# controls.net
KiCad netlist of a schematic drawn in EAGLE
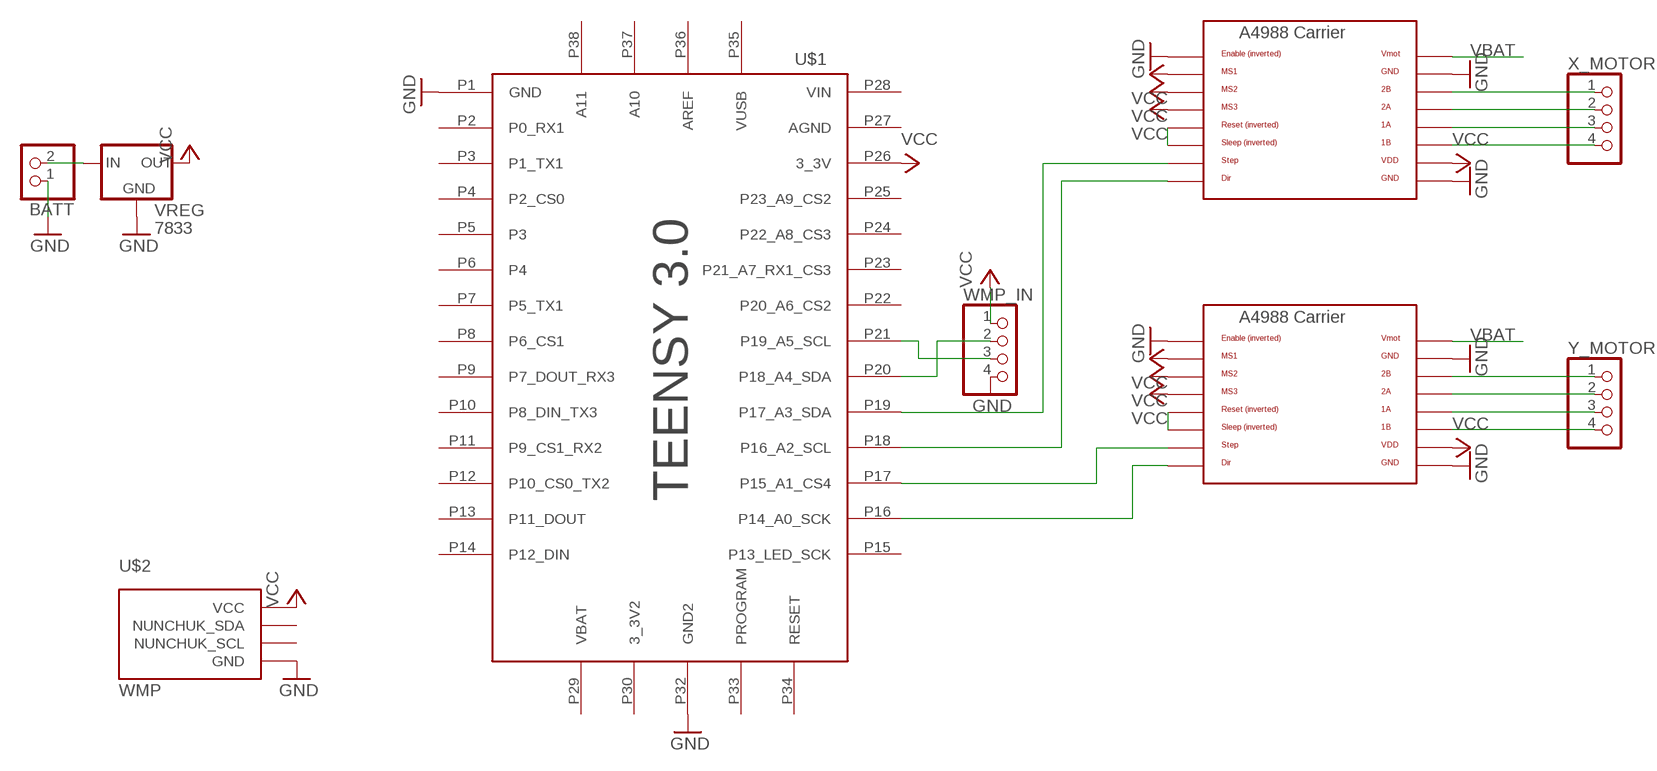
[diagram p0: schematic, sheet 1]

(export (version "E")
  (design (tool "Eeschema 10.0.6"))
  (components
    (comp (ref "BATT")
      (value "PINHD-1X2")
      (footprint "eagle-import:1X02")
      (libsource (lib "eagle-import") (part "PINHD-1X2"))
    )
    (comp (ref "U$1")
      (value "TEENSY3")
      (footprint "eagle-import:TEENSY3_BRD")
      (libsource (lib "eagle-import") (part "TEENSY3"))
    )
    (comp (ref "U$2")
      (value "WMP")
      (footprint "eagle-import:WMP")
      (libsource (lib "eagle-import") (part "WMP"))
    )
    (comp (ref "VREG")
      (value "7833")
      (footprint "eagle-import:78LXX")
      (libsource (lib "eagle-import") (part "78LXX"))
    )
    (comp (ref "WMP_IN")
      (value "PINHD-1X4/90")
      (footprint "eagle-import:1X04_90")
      (libsource (lib "eagle-import") (part "PINHD-1X4/90"))
    )
    (comp (ref "X_DRIVE")
      (value "POLOLU_A4983CARRIER")
      (footprint "eagle-import:A4988BREAKOUT")
      (libsource (lib "eagle-import") (part "POLOLU_A4983CARRIER"))
    )
    (comp (ref "X_MOTOR")
      (value "PINHD-1X4/90")
      (footprint "eagle-import:1X04_90")
      (libsource (lib "eagle-import") (part "PINHD-1X4/90"))
    )
    (comp (ref "Y_DRIVE")
      (value "POLOLU_A4983CARRIER")
      (footprint "eagle-import:A4988BREAKOUT")
      (libsource (lib "eagle-import") (part "POLOLU_A4983CARRIER"))
    )
    (comp (ref "Y_MOTOR")
      (value "PINHD-1X4/90")
      (footprint "eagle-import:1X04_90")
      (libsource (lib "eagle-import") (part "PINHD-1X4/90"))
    )
  )
  (nets
    (net (code "1") (name "/VBAT") (class "Default")
      (node (ref "BATT") (pin "2") (pinfunction "2_2") (pintype "passive"))
      (node (ref "VREG") (pin "IN") (pinfunction "IN_IN") (pintype "input"))
      (node (ref "X_DRIVE") (pin "VMOT") (pinfunction "VMOT_VMOT") (pintype "power_in"))
      (node (ref "Y_DRIVE") (pin "VMOT") (pinfunction "VMOT_VMOT") (pintype "power_in"))
    )
    (net (code "2") (name "GND") (class "Default")
      (node (ref "BATT") (pin "1") (pinfunction "1_1") (pintype "passive"))
      (node (ref "U$1") (pin "P1") (pinfunction "GND_P1") (pintype "bidirectional"))
      (node (ref "U$1") (pin "P32") (pinfunction "GND2_P32") (pintype "bidirectional"))
      (node (ref "U$2") (pin "GND") (pinfunction "GND_GND") (pintype "power_in"))
      (node (ref "VREG") (pin "GND") (pinfunction "GND_GND") (pintype "input"))
      (node (ref "WMP_IN") (pin "4") (pinfunction "4_4") (pintype "passive"))
      (node (ref "X_DRIVE") (pin "EN") (pinfunction "EN_EN") (pintype "input"))
      (node (ref "X_DRIVE") (pin "GND") (pinfunction "GND_GND") (pintype "power_in"))
      (node (ref "X_DRIVE") (pin "GND@0") (pinfunction "GND_GND@0") (pintype "power_in"))
      (node (ref "Y_DRIVE") (pin "EN") (pinfunction "EN_EN") (pintype "input"))
      (node (ref "Y_DRIVE") (pin "GND") (pinfunction "GND_GND") (pintype "power_in"))
      (node (ref "Y_DRIVE") (pin "GND@0") (pinfunction "GND_GND@0") (pintype "power_in"))
    )
    (net (code "3") (name "Net-(U$1-P14_A0_SCK)") (class "Default")
      (node (ref "U$1") (pin "P16") (pinfunction "P14_A0_SCK_P16") (pintype "bidirectional"))
      (node (ref "Y_DRIVE") (pin "DIR") (pinfunction "DIR_DIR") (pintype "input"))
    )
    (net (code "4") (name "Net-(U$1-P15_A1_CS4)") (class "Default")
      (node (ref "U$1") (pin "P17") (pinfunction "P15_A1_CS4_P17") (pintype "bidirectional"))
      (node (ref "Y_DRIVE") (pin "STEP") (pinfunction "STEP_STEP") (pintype "input"))
    )
    (net (code "5") (name "Net-(U$1-P16_A2_SCL)") (class "Default")
      (node (ref "U$1") (pin "P18") (pinfunction "P16_A2_SCL_P18") (pintype "bidirectional"))
      (node (ref "X_DRIVE") (pin "DIR") (pinfunction "DIR_DIR") (pintype "input"))
    )
    (net (code "6") (name "Net-(U$1-P17_A3_SDA)") (class "Default")
      (node (ref "U$1") (pin "P19") (pinfunction "P17_A3_SDA_P19") (pintype "bidirectional"))
      (node (ref "X_DRIVE") (pin "STEP") (pinfunction "STEP_STEP") (pintype "input"))
    )
    (net (code "7") (name "Net-(U$1-P18_A4_SDA)") (class "Default")
      (node (ref "U$1") (pin "P20") (pinfunction "P18_A4_SDA_P20") (pintype "bidirectional"))
      (node (ref "WMP_IN") (pin "2") (pinfunction "2_2") (pintype "passive"))
    )
    (net (code "8") (name "Net-(U$1-P19_A5_SCL)") (class "Default")
      (node (ref "U$1") (pin "P21") (pinfunction "P19_A5_SCL_P21") (pintype "bidirectional"))
      (node (ref "WMP_IN") (pin "3") (pinfunction "3_3") (pintype "passive"))
    )
    (net (code "9") (name "Net-(X_DRIVE-Pad1A)") (class "Default")
      (node (ref "X_DRIVE") (pin "1A") (pinfunction "1A_1A") (pintype "output"))
      (node (ref "X_MOTOR") (pin "3") (pinfunction "3_3") (pintype "passive"))
    )
    (net (code "10") (name "Net-(X_DRIVE-Pad1B)") (class "Default")
      (node (ref "X_DRIVE") (pin "1B") (pinfunction "1B_1B") (pintype "output"))
      (node (ref "X_MOTOR") (pin "4") (pinfunction "4_4") (pintype "passive"))
    )
    (net (code "11") (name "Net-(X_DRIVE-Pad2A)") (class "Default")
      (node (ref "X_DRIVE") (pin "2A") (pinfunction "2A_2A") (pintype "output"))
      (node (ref "X_MOTOR") (pin "2") (pinfunction "2_2") (pintype "passive"))
    )
    (net (code "12") (name "Net-(X_DRIVE-Pad2B)") (class "Default")
      (node (ref "X_DRIVE") (pin "2B") (pinfunction "2B_2B") (pintype "output"))
      (node (ref "X_MOTOR") (pin "1") (pinfunction "1_1") (pintype "passive"))
    )
    (net (code "13") (name "Net-(X_DRIVE-SLEEP)") (class "Default")
      (node (ref "X_DRIVE") (pin "RST") (pinfunction "RST_RST") (pintype "input"))
      (node (ref "X_DRIVE") (pin "SLP") (pinfunction "SLEEP_SLP") (pintype "input"))
    )
    (net (code "14") (name "Net-(Y_DRIVE-Pad1A)") (class "Default")
      (node (ref "Y_DRIVE") (pin "1A") (pinfunction "1A_1A") (pintype "output"))
      (node (ref "Y_MOTOR") (pin "3") (pinfunction "3_3") (pintype "passive"))
    )
    (net (code "15") (name "Net-(Y_DRIVE-Pad1B)") (class "Default")
      (node (ref "Y_DRIVE") (pin "1B") (pinfunction "1B_1B") (pintype "output"))
      (node (ref "Y_MOTOR") (pin "4") (pinfunction "4_4") (pintype "passive"))
    )
    (net (code "16") (name "Net-(Y_DRIVE-Pad2A)") (class "Default")
      (node (ref "Y_DRIVE") (pin "2A") (pinfunction "2A_2A") (pintype "output"))
      (node (ref "Y_MOTOR") (pin "2") (pinfunction "2_2") (pintype "passive"))
    )
    (net (code "17") (name "Net-(Y_DRIVE-Pad2B)") (class "Default")
      (node (ref "Y_DRIVE") (pin "2B") (pinfunction "2B_2B") (pintype "output"))
      (node (ref "Y_MOTOR") (pin "1") (pinfunction "1_1") (pintype "passive"))
    )
    (net (code "18") (name "Net-(Y_DRIVE-SLEEP)") (class "Default")
      (node (ref "Y_DRIVE") (pin "RST") (pinfunction "RST_RST") (pintype "input"))
      (node (ref "Y_DRIVE") (pin "SLP") (pinfunction "SLEEP_SLP") (pintype "input"))
    )
    (net (code "19") (name "VCC") (class "Default")
      (node (ref "U$1") (pin "P26") (pinfunction "3_3V_P26") (pintype "bidirectional"))
      (node (ref "U$2") (pin "VCC") (pinfunction "VCC_VCC") (pintype "power_in"))
      (node (ref "VREG") (pin "OUT") (pinfunction "OUT_OUT") (pintype "passive"))
      (node (ref "WMP_IN") (pin "1") (pinfunction "1_1") (pintype "passive"))
      (node (ref "X_DRIVE") (pin "MS1") (pinfunction "MS1_MS1") (pintype "input"))
      (node (ref "X_DRIVE") (pin "MS2") (pinfunction "MS2_MS2") (pintype "input"))
      (node (ref "X_DRIVE") (pin "MS3") (pinfunction "MS3_MS3") (pintype "input"))
      (node (ref "X_DRIVE") (pin "VDD") (pinfunction "VDD_VDD") (pintype "power_in"))
      (node (ref "Y_DRIVE") (pin "MS1") (pinfunction "MS1_MS1") (pintype "input"))
      (node (ref "Y_DRIVE") (pin "MS2") (pinfunction "MS2_MS2") (pintype "input"))
      (node (ref "Y_DRIVE") (pin "MS3") (pinfunction "MS3_MS3") (pintype "input"))
      (node (ref "Y_DRIVE") (pin "VDD") (pinfunction "VDD_VDD") (pintype "power_in"))
    )
    (net (code "20") (name "unconnected-(U$1-3_3V2-PadP30)") (class "Default")
      (node (ref "U$1") (pin "P30") (pinfunction "3_3V2_P30") (pintype "bidirectional"))
    )
    (net (code "21") (name "unconnected-(U$1-A10-PadP37)") (class "Default")
      (node (ref "U$1") (pin "P37") (pinfunction "A10_P37") (pintype "bidirectional"))
    )
    (net (code "22") (name "unconnected-(U$1-A11-PadP38)") (class "Default")
      (node (ref "U$1") (pin "P38") (pinfunction "A11_P38") (pintype "bidirectional"))
    )
    (net (code "23") (name "unconnected-(U$1-AGND-PadP27)") (class "Default")
      (node (ref "U$1") (pin "P27") (pinfunction "AGND_P27") (pintype "bidirectional"))
    )
    (net (code "24") (name "unconnected-(U$1-AREF-PadP36)") (class "Default")
      (node (ref "U$1") (pin "P36") (pinfunction "AREF_P36") (pintype "bidirectional"))
    )
    (net (code "25") (name "unconnected-(U$1-P0_RX1-PadP2)") (class "Default")
      (node (ref "U$1") (pin "P2") (pinfunction "P0_RX1_P2") (pintype "bidirectional"))
    )
    (net (code "26") (name "unconnected-(U$1-P1_TX1-PadP3)") (class "Default")
      (node (ref "U$1") (pin "P3") (pinfunction "P1_TX1_P3") (pintype "bidirectional"))
    )
    (net (code "27") (name "unconnected-(U$1-P2_CS0-PadP4)") (class "Default")
      (node (ref "U$1") (pin "P4") (pinfunction "P2_CS0_P4") (pintype "bidirectional"))
    )
    (net (code "28") (name "unconnected-(U$1-P3-PadP5)") (class "Default")
      (node (ref "U$1") (pin "P5") (pinfunction "P3_P5") (pintype "bidirectional"))
    )
    (net (code "29") (name "unconnected-(U$1-P4-PadP6)") (class "Default")
      (node (ref "U$1") (pin "P6") (pinfunction "P4_P6") (pintype "bidirectional"))
    )
    (net (code "30") (name "unconnected-(U$1-P5_TX1-PadP7)") (class "Default")
      (node (ref "U$1") (pin "P7") (pinfunction "P5_TX1_P7") (pintype "bidirectional"))
    )
    (net (code "31") (name "unconnected-(U$1-P6_CS1-PadP8)") (class "Default")
      (node (ref "U$1") (pin "P8") (pinfunction "P6_CS1_P8") (pintype "bidirectional"))
    )
    (net (code "32") (name "unconnected-(U$1-P7_DOUT_RX3-PadP9)") (class "Default")
      (node (ref "U$1") (pin "P9") (pinfunction "P7_DOUT_RX3_P9") (pintype "bidirectional"))
    )
    (net (code "33") (name "unconnected-(U$1-P8_DIN_TX3-PadP10)") (class "Default")
      (node (ref "U$1") (pin "P10") (pinfunction "P8_DIN_TX3_P10") (pintype "bidirectional"))
    )
    (net (code "34") (name "unconnected-(U$1-P9_CS1_RX2-PadP11)") (class "Default")
      (node (ref "U$1") (pin "P11") (pinfunction "P9_CS1_RX2_P11") (pintype "bidirectional"))
    )
    (net (code "35") (name "unconnected-(U$1-P10_CS0_TX2-PadP12)") (class "Default")
      (node (ref "U$1") (pin "P12") (pinfunction "P10_CS0_TX2_P12") (pintype "bidirectional"))
    )
    (net (code "36") (name "unconnected-(U$1-P11_DOUT-PadP13)") (class "Default")
      (node (ref "U$1") (pin "P13") (pinfunction "P11_DOUT_P13") (pintype "bidirectional"))
    )
    (net (code "37") (name "unconnected-(U$1-P12_DIN-PadP14)") (class "Default")
      (node (ref "U$1") (pin "P14") (pinfunction "P12_DIN_P14") (pintype "bidirectional"))
    )
    (net (code "38") (name "unconnected-(U$1-P13_LED_SCK-PadP15)") (class "Default")
      (node (ref "U$1") (pin "P15") (pinfunction "P13_LED_SCK_P15") (pintype "bidirectional"))
    )
    (net (code "39") (name "unconnected-(U$1-P20_A6_CS2-PadP22)") (class "Default")
      (node (ref "U$1") (pin "P22") (pinfunction "P20_A6_CS2_P22") (pintype "bidirectional"))
    )
    (net (code "40") (name "unconnected-(U$1-P21_A7_RX1_CS3-PadP23)") (class "Default")
      (node (ref "U$1") (pin "P23") (pinfunction "P21_A7_RX1_CS3_P23") (pintype "bidirectional"))
    )
    (net (code "41") (name "unconnected-(U$1-P22_A8_CS3-PadP24)") (class "Default")
      (node (ref "U$1") (pin "P24") (pinfunction "P22_A8_CS3_P24") (pintype "bidirectional"))
    )
    (net (code "42") (name "unconnected-(U$1-P23_A9_CS2-PadP25)") (class "Default")
      (node (ref "U$1") (pin "P25") (pinfunction "P23_A9_CS2_P25") (pintype "bidirectional"))
    )
    (net (code "43") (name "unconnected-(U$1-PROGRAM-PadP33)") (class "Default")
      (node (ref "U$1") (pin "P33") (pinfunction "PROGRAM_P33") (pintype "bidirectional"))
    )
    (net (code "44") (name "unconnected-(U$1-RESET-PadP34)") (class "Default")
      (node (ref "U$1") (pin "P34") (pinfunction "RESET_P34") (pintype "bidirectional"))
    )
    (net (code "45") (name "unconnected-(U$1-VBAT-PadP29)") (class "Default")
      (node (ref "U$1") (pin "P29") (pinfunction "VBAT_P29") (pintype "bidirectional"))
    )
    (net (code "46") (name "unconnected-(U$1-VIN-PadP28)") (class "Default")
      (node (ref "U$1") (pin "P28") (pinfunction "VIN_P28") (pintype "bidirectional"))
    )
    (net (code "47") (name "unconnected-(U$1-VUSB-PadP35)") (class "Default")
      (node (ref "U$1") (pin "P35") (pinfunction "VUSB_P35") (pintype "bidirectional"))
    )
    (net (code "48") (name "unconnected-(U$2-NUNCHUK_SCL-PadSCL)") (class "Default")
      (node (ref "U$2") (pin "SCL") (pinfunction "NUNCHUK_SCL_SCL") (pintype "bidirectional"))
    )
    (net (code "49") (name "unconnected-(U$2-NUNCHUK_SDA-PadSDA)") (class "Default")
      (node (ref "U$2") (pin "SDA") (pinfunction "NUNCHUK_SDA_SDA") (pintype "bidirectional"))
    )
  )
)
